# Buck.net
KiCad netlist of a schematic drawn in Altium Designer
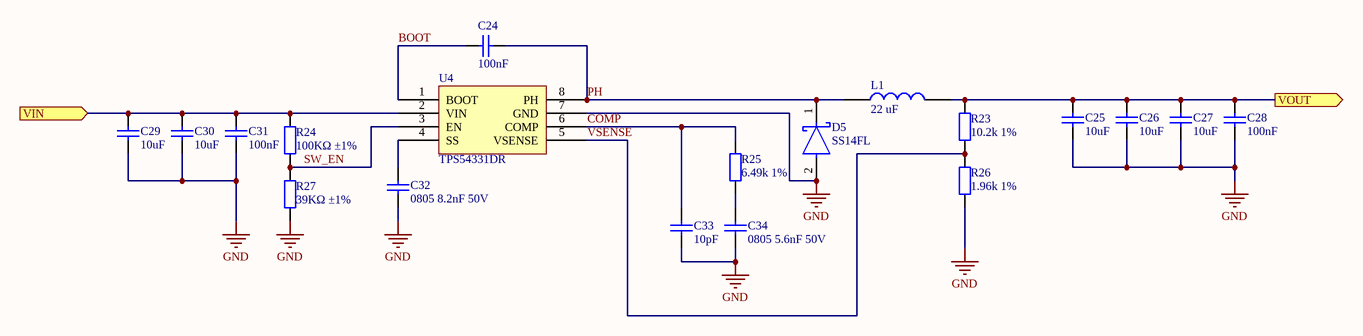
[diagram p0: Buck.SchDoc]

(export (version "E")
  (design (tool "Eeschema 10.0.6"))
  (components
    (comp (ref "C24")
      (value "100nF")
      (footprint "0603_C")
      (description "Chip capacitors")
      (fields (field (name "MANUFACTURER") "YAGEO") (field (name "PARTNUMBER") "CC0603KRX7R9BB104"))
      (libsource (lib "Miscellaneous Devices LC") (part "0603 100nF (104) 10% 50V"))
    )
    (comp (ref "C25")
      (value "10uF")
      (footprint "0603_C")
      (description "Chip capacitors")
      (fields
        (field (name "MANUFACTURER") "Samsung Electro-Mechanics")
        (field (name "PARTNUMBER") "CL10A106KP8NNNC")
      )
      (libsource (lib "Miscellaneous Devices LC") (part "0603 10uF (106) 10% 10V"))
    )
    (comp (ref "C26")
      (value "10uF")
      (footprint "0603_C")
      (description "Chip capacitors")
      (fields
        (field (name "MANUFACTURER") "Samsung Electro-Mechanics")
        (field (name "PARTNUMBER") "CL10A106KP8NNNC")
      )
      (libsource (lib "Miscellaneous Devices LC") (part "0603 10uF (106) 10% 10V"))
    )
    (comp (ref "C27")
      (value "10uF")
      (footprint "0603_C")
      (description "Chip capacitors")
      (fields
        (field (name "MANUFACTURER") "Samsung Electro-Mechanics")
        (field (name "PARTNUMBER") "CL10A106KP8NNNC")
      )
      (libsource (lib "Miscellaneous Devices LC") (part "0603 10uF (106) 10% 10V"))
    )
    (comp (ref "C28")
      (value "100nF")
      (footprint "0603_C")
      (description "Chip capacitors")
      (fields (field (name "MANUFACTURER") "YAGEO") (field (name "PARTNUMBER") "CC0603KRX7R9BB104"))
      (libsource (lib "Miscellaneous Devices LC") (part "0603 100nF (104) 10% 50V"))
    )
    (comp (ref "C29")
      (value "10uF")
      (footprint "0805_C")
      (description "Chip capacitors")
      (fields
        (field (name "MANUFACTURER") "Samsung Electro-Mechanics")
        (field (name "PARTNUMBER") "CL21A106KAYNNNE")
      )
      (libsource (lib "Miscellaneous Devices LC") (part "0805 10uF (106) 10% 25V"))
    )
    (comp (ref "C30")
      (value "10uF")
      (footprint "0805_C")
      (description "Chip capacitors")
      (fields
        (field (name "MANUFACTURER") "Samsung Electro-Mechanics")
        (field (name "PARTNUMBER") "CL21A106KAYNNNE")
      )
      (libsource (lib "Miscellaneous Devices LC") (part "0805 10uF (106) 10% 25V"))
    )
    (comp (ref "C31")
      (value "100nF")
      (footprint "0603_C")
      (description "Chip capacitors")
      (fields (field (name "MANUFACTURER") "YAGEO") (field (name "PARTNUMBER") "CC0603KRX7R9BB104"))
      (libsource (lib "Miscellaneous Devices LC") (part "0603 100nF (104) 10% 50V"))
    )
    (comp (ref "C32")
      (value "0805 8.2nF 50V")
      (footprint "Miscellaneous Devices LC:0805_C")
      (fields (field (name "PARTNUMBER") "CL21B822KBANNNC"))
      (libsource (lib "misc") (part "0805 8.2nF 50V"))
    )
    (comp (ref "C33")
      (value "10pF")
      (footprint "0603_C")
      (description "Chip capacitors")
      (fields
        (field (name "MANUFACTURER") "Samsung Electro-Mechanics")
        (field (name "PARTNUMBER") "CL10C100JB8NNNC")
      )
      (libsource (lib "Miscellaneous Devices LC") (part "0603 10pF (100) 5% 50V"))
    )
    (comp (ref "C34")
      (value "0805 5.6nF 50V")
      (footprint "Miscellaneous Devices LC:0805_C")
      (fields (field (name "PARTNUMBER") "CL21B562KBANNNC"))
      (libsource (lib "misc") (part "0805 5.6nF 50V"))
    )
    (comp (ref "D5")
      (value "SS14FL")
      (footprint "FP-425AD-MFG")
      (description "DIODE SCHOTTKY 40V 1A SOD123F")
      (fields
        (field (name "MANUFACTURER") "ON Semiconductor")
        (field (name "OCTOPART") "https://octopart.com/ss14fl-on+semiconductor-84331601")
      )
      (libsource (lib "Altium Content Vault") (part "c1678fac7984e62e0809fbf79c06691"))
    )
    (comp (ref "L1")
      (value "22 uF")
      (footprint "DR74:COBU-DR74-4R7-R_V")
      (libsource (lib "SWRB1204S-220MT") (part "SRP6540-5R6M"))
    )
    (comp (ref "R23")
      (value "10.2k 1%")
      (footprint "Miscellaneous Devices LC:1206_R")
      (fields (field (name "PARTNUMBER") "1206W4F1022T5E"))
      (libsource (lib "misc") (part "1206 10.2k 1%"))
    )
    (comp (ref "R24")
      (value "100KΩ ±1%")
      (footprint "0805_R")
      (description "Chip resistor")
      (fields (field (name "MANUFACTURER") "Uniroyal Elec") (field (name "POWER") "1/8W"))
      (libsource (lib "Miscellaneous Devices LC") (part "0805 100K (1003) 1%"))
    )
    (comp (ref "R25")
      (value "6.49k 1%")
      (footprint "Miscellaneous Devices LC:0805_R")
      (fields (field (name "PARTNUMBER") "0805W8F6491T5E"))
      (libsource (lib "misc") (part "0805 6.49k 1%"))
    )
    (comp (ref "R26")
      (value "1.96k 1%")
      (footprint "Miscellaneous Devices LC:1206_R")
      (fields (field (name "PARTNUMBER") "1206W4F1022T5E"))
      (libsource (lib "misc") (part "1206 1.96k 1%"))
    )
    (comp (ref "R27")
      (value "39KΩ ±1%")
      (footprint "0805_R")
      (description "Chip resistor")
      (fields (field (name "MANUFACTURER") "Uniroyal Elec") (field (name "POWER") "1/8W"))
      (libsource (lib "Miscellaneous Devices LC") (part "0805 39K (3902) 1%"))
    )
    (comp (ref "U4")
      (value "TPS54331DR")
      (footprint "SOIC-8_150mil")
      (description "DC-DC芯片")
      (libsource (lib "Miscellaneous Devices LC") (part "TPS54331DR_[C9865]"))
    )
  )
  (nets
    (net (code "1") (name "/BOOT") (class "Default")
      (node (ref "C24") (pin "2") (pinfunction "2_2") (pintype "passive"))
      (node (ref "U4") (pin "1") (pinfunction "BOOT_1") (pintype "passive"))
    )
    (net (code "2") (name "/COMP") (class "Default")
      (node (ref "C33") (pin "2") (pinfunction "2_2") (pintype "passive"))
      (node (ref "R25") (pin "2") (pinfunction "2_2") (pintype "passive"))
      (node (ref "U4") (pin "6") (pinfunction "COMP_6") (pintype "passive"))
    )
    (net (code "3") (name "/PH") (class "Default")
      (node (ref "C24") (pin "1") (pinfunction "1_1") (pintype "passive"))
      (node (ref "D5") (pin "1") (pinfunction "C_1") (pintype "passive"))
      (node (ref "L1") (pin "1") (pinfunction "1_1") (pintype "passive"))
      (node (ref "U4") (pin "8") (pinfunction "PH_8") (pintype "passive"))
    )
    (net (code "4") (name "/SW_EN") (class "Default")
      (node (ref "R24") (pin "2") (pinfunction "2_2") (pintype "passive"))
      (node (ref "R27") (pin "2") (pinfunction "2_2") (pintype "passive"))
      (node (ref "U4") (pin "3") (pinfunction "EN_3") (pintype "passive"))
    )
    (net (code "5") (name "/VIN") (class "Default")
      (node (ref "C29") (pin "2") (pinfunction "2_2") (pintype "passive"))
      (node (ref "C30") (pin "2") (pinfunction "2_2") (pintype "passive"))
      (node (ref "C31") (pin "2") (pinfunction "2_2") (pintype "passive"))
      (node (ref "R24") (pin "1") (pinfunction "1_1") (pintype "passive"))
      (node (ref "U4") (pin "2") (pinfunction "VIN_2") (pintype "passive"))
    )
    (net (code "6") (name "/VOUT") (class "Default")
      (node (ref "C25") (pin "2") (pinfunction "2_2") (pintype "passive"))
      (node (ref "C26") (pin "2") (pinfunction "2_2") (pintype "passive"))
      (node (ref "C27") (pin "2") (pinfunction "2_2") (pintype "passive"))
      (node (ref "C28") (pin "2") (pinfunction "2_2") (pintype "passive"))
      (node (ref "L1") (pin "2") (pinfunction "2_2") (pintype "passive"))
      (node (ref "R23") (pin "1") (pinfunction "1_1") (pintype "passive"))
    )
    (net (code "7") (name "/VSENSE") (class "Default")
      (node (ref "R23") (pin "2") (pinfunction "2_2") (pintype "passive"))
      (node (ref "R26") (pin "2") (pinfunction "2_2") (pintype "passive"))
      (node (ref "U4") (pin "5") (pinfunction "VSENSE_5") (pintype "passive"))
    )
    (net (code "8") (name "GND") (class "Default")
      (node (ref "C25") (pin "1") (pinfunction "1_1") (pintype "passive"))
      (node (ref "C26") (pin "1") (pinfunction "1_1") (pintype "passive"))
      (node (ref "C27") (pin "1") (pinfunction "1_1") (pintype "passive"))
      (node (ref "C28") (pin "1") (pinfunction "1_1") (pintype "passive"))
      (node (ref "C29") (pin "1") (pinfunction "1_1") (pintype "passive"))
      (node (ref "C30") (pin "1") (pinfunction "1_1") (pintype "passive"))
      (node (ref "C31") (pin "1") (pinfunction "1_1") (pintype "passive"))
      (node (ref "C32") (pin "1") (pinfunction "1_1") (pintype "passive"))
      (node (ref "C33") (pin "1") (pinfunction "1_1") (pintype "passive"))
      (node (ref "C34") (pin "1") (pinfunction "1_1") (pintype "passive"))
      (node (ref "D5") (pin "2") (pinfunction "A_2") (pintype "passive"))
      (node (ref "R26") (pin "1") (pinfunction "1_1") (pintype "passive"))
      (node (ref "R27") (pin "1") (pinfunction "1_1") (pintype "passive"))
      (node (ref "U4") (pin "7") (pinfunction "GND_7") (pintype "passive"))
    )
    (net (code "9") (name "Net-(C34-Pad2)") (class "Default")
      (node (ref "C34") (pin "2") (pinfunction "2_2") (pintype "passive"))
      (node (ref "R25") (pin "1") (pinfunction "1_1") (pintype "passive"))
    )
    (net (code "10") (name "Net-(U4-SS)") (class "Default")
      (node (ref "C32") (pin "2") (pinfunction "2_2") (pintype "passive"))
      (node (ref "U4") (pin "4") (pinfunction "SS_4") (pintype "passive"))
    )
  )
)
